# LEDControllerBoard.net
KiCad netlist of a schematic drawn in EAGLE
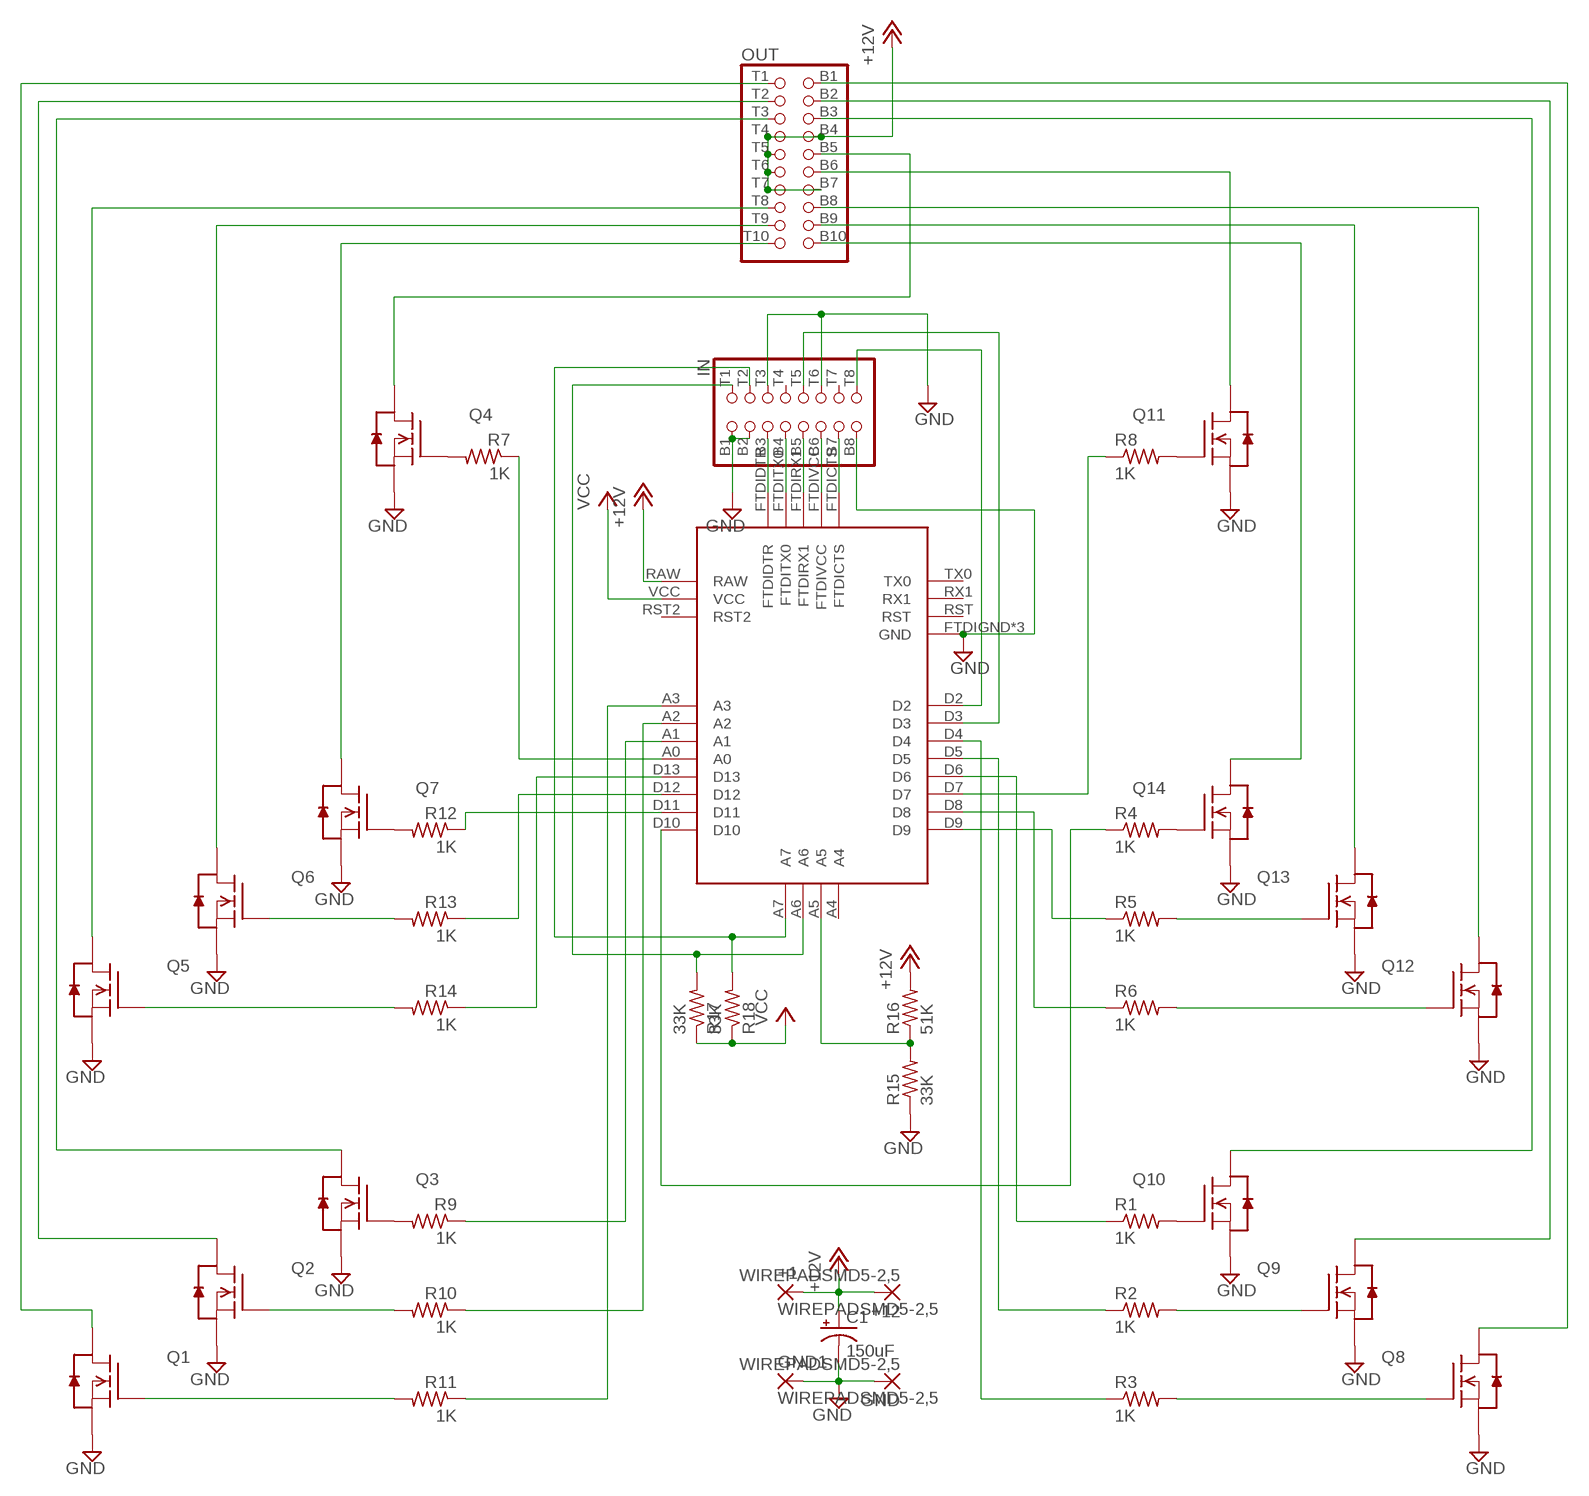
[diagram p0: schematic, sheet 1]

(export (version "E")
  (design (tool "Eeschema 10.0.6"))
  (components
    (comp (ref "+1")
      (value "WIREPADSMD5-2,5")
      (footprint "eagle-import:5-2,5")
      (libsource (lib "eagle-import") (part "WIREPADSMD5-2,5"))
    )
    (comp (ref "+12")
      (value "WIREPADSMD5-2,5")
      (footprint "eagle-import:5-2,5")
      (libsource (lib "eagle-import") (part "WIREPADSMD5-2,5"))
    )
    (comp (ref "C1")
      (value "150uF")
      (footprint "eagle-import:PANASONIC_D")
      (libsource (lib "eagle-import") (part "CPOL-USD"))
    )
    (comp (ref "GND")
      (value "WIREPADSMD5-2,5")
      (footprint "eagle-import:5-2,5")
      (libsource (lib "eagle-import") (part "WIREPADSMD5-2,5"))
    )
    (comp (ref "GND1")
      (value "WIREPADSMD5-2,5")
      (footprint "eagle-import:5-2,5")
      (libsource (lib "eagle-import") (part "WIREPADSMD5-2,5"))
    )
    (comp (ref "IN")
      (value "PINHD-2X8/EDGE")
      (footprint "eagle-import:2X8_EDGE")
      (libsource (lib "eagle-import") (part "PINHD-2X8/EDGE"))
    )
    (comp (ref "OUT")
      (value "PINHD-2X10/EDGE")
      (footprint "eagle-import:2X10_EDGE")
      (libsource (lib "eagle-import") (part "PINHD-2X10/EDGE"))
    )
    (comp (ref "Q1")
      (value "FDC653NSSOT6")
      (footprint "eagle-import:SSOT6")
      (libsource (lib "eagle-import") (part "FDC653NSSOT6"))
    )
    (comp (ref "Q2")
      (value "FDC653NSSOT6")
      (footprint "eagle-import:SSOT6")
      (libsource (lib "eagle-import") (part "FDC653NSSOT6"))
    )
    (comp (ref "Q3")
      (value "FDC653NSSOT6")
      (footprint "eagle-import:SSOT6")
      (libsource (lib "eagle-import") (part "FDC653NSSOT6"))
    )
    (comp (ref "Q4")
      (value "FDC653NSSOT6")
      (footprint "eagle-import:SSOT6")
      (libsource (lib "eagle-import") (part "FDC653NSSOT6"))
    )
    (comp (ref "Q5")
      (value "FDC653NSSOT6")
      (footprint "eagle-import:SSOT6")
      (libsource (lib "eagle-import") (part "FDC653NSSOT6"))
    )
    (comp (ref "Q6")
      (value "FDC653NSSOT6")
      (footprint "eagle-import:SSOT6")
      (libsource (lib "eagle-import") (part "FDC653NSSOT6"))
    )
    (comp (ref "Q7")
      (value "FDC653NSSOT6")
      (footprint "eagle-import:SSOT6")
      (libsource (lib "eagle-import") (part "FDC653NSSOT6"))
    )
    (comp (ref "Q8")
      (value "FDC653NSSOT6")
      (footprint "eagle-import:SSOT6")
      (libsource (lib "eagle-import") (part "FDC653NSSOT6"))
    )
    (comp (ref "Q9")
      (value "FDC653NSSOT6")
      (footprint "eagle-import:SSOT6")
      (libsource (lib "eagle-import") (part "FDC653NSSOT6"))
    )
    (comp (ref "Q10")
      (value "FDC653NSSOT6")
      (footprint "eagle-import:SSOT6")
      (libsource (lib "eagle-import") (part "FDC653NSSOT6"))
    )
    (comp (ref "Q11")
      (value "FDC653NSSOT6")
      (footprint "eagle-import:SSOT6")
      (libsource (lib "eagle-import") (part "FDC653NSSOT6"))
    )
    (comp (ref "Q12")
      (value "FDC653NSSOT6")
      (footprint "eagle-import:SSOT6")
      (libsource (lib "eagle-import") (part "FDC653NSSOT6"))
    )
    (comp (ref "Q13")
      (value "FDC653NSSOT6")
      (footprint "eagle-import:SSOT6")
      (libsource (lib "eagle-import") (part "FDC653NSSOT6"))
    )
    (comp (ref "Q14")
      (value "FDC653NSSOT6")
      (footprint "eagle-import:SSOT6")
      (libsource (lib "eagle-import") (part "FDC653NSSOT6"))
    )
    (comp (ref "R1")
      (value "1K")
      (footprint "eagle-import:R0603")
      (libsource (lib "eagle-import") (part "R-US_R0603"))
    )
    (comp (ref "R2")
      (value "1K")
      (footprint "eagle-import:R0603")
      (libsource (lib "eagle-import") (part "R-US_R0603"))
    )
    (comp (ref "R3")
      (value "1K")
      (footprint "eagle-import:R0603")
      (libsource (lib "eagle-import") (part "R-US_R0603"))
    )
    (comp (ref "R4")
      (value "1K")
      (footprint "eagle-import:R0603")
      (libsource (lib "eagle-import") (part "R-US_R0603"))
    )
    (comp (ref "R5")
      (value "1K")
      (footprint "eagle-import:R0603")
      (libsource (lib "eagle-import") (part "R-US_R0603"))
    )
    (comp (ref "R6")
      (value "1K")
      (footprint "eagle-import:R0603")
      (libsource (lib "eagle-import") (part "R-US_R0603"))
    )
    (comp (ref "R7")
      (value "1K")
      (footprint "eagle-import:R0603")
      (libsource (lib "eagle-import") (part "R-US_R0603"))
    )
    (comp (ref "R8")
      (value "1K")
      (footprint "eagle-import:R0603")
      (libsource (lib "eagle-import") (part "R-US_R0603"))
    )
    (comp (ref "R9")
      (value "1K")
      (footprint "eagle-import:R0603")
      (libsource (lib "eagle-import") (part "R-US_R0603"))
    )
    (comp (ref "R10")
      (value "1K")
      (footprint "eagle-import:R0603")
      (libsource (lib "eagle-import") (part "R-US_R0603"))
    )
    (comp (ref "R11")
      (value "1K")
      (footprint "eagle-import:R0603")
      (libsource (lib "eagle-import") (part "R-US_R0603"))
    )
    (comp (ref "R12")
      (value "1K")
      (footprint "eagle-import:R0603")
      (libsource (lib "eagle-import") (part "R-US_R0603"))
    )
    (comp (ref "R13")
      (value "1K")
      (footprint "eagle-import:R0603")
      (libsource (lib "eagle-import") (part "R-US_R0603"))
    )
    (comp (ref "R14")
      (value "1K")
      (footprint "eagle-import:R0603")
      (libsource (lib "eagle-import") (part "R-US_R0603"))
    )
    (comp (ref "R15")
      (value "33K")
      (footprint "eagle-import:R0603")
      (libsource (lib "eagle-import") (part "R-US_R0603"))
    )
    (comp (ref "R16")
      (value "51K")
      (footprint "eagle-import:R0603")
      (libsource (lib "eagle-import") (part "R-US_R0603"))
    )
    (comp (ref "R17")
      (value "33K")
      (footprint "eagle-import:R0603")
      (libsource (lib "eagle-import") (part "R-US_R0603"))
    )
    (comp (ref "R18")
      (value "33K")
      (footprint "eagle-import:R0603")
      (libsource (lib "eagle-import") (part "R-US_R0603"))
    )
    (comp (ref "U$15")
      (value "ARDUINOPROMINI")
      (footprint "eagle-import:ARDUINOPROMINI")
      (libsource (lib "eagle-import") (part "ARDUINOPROMINI"))
    )
  )
  (nets
    (net (code "1") (name "+12V") (class "Default")
      (node (ref "+1") (pin "1") (pinfunction "P_1") (pintype "passive"))
      (node (ref "+12") (pin "1") (pinfunction "P_1") (pintype "passive"))
      (node (ref "C1") (pin "+") (pinfunction "+_+") (pintype "passive"))
      (node (ref "OUT") (pin "B4") (pinfunction "8_B4") (pintype "passive"))
      (node (ref "OUT") (pin "B7") (pinfunction "14_B7") (pintype "passive"))
      (node (ref "OUT") (pin "T4") (pinfunction "7_T4") (pintype "passive"))
      (node (ref "OUT") (pin "T5") (pinfunction "9_T5") (pintype "passive"))
      (node (ref "OUT") (pin "T6") (pinfunction "11_T6") (pintype "passive"))
      (node (ref "OUT") (pin "T7") (pinfunction "13_T7") (pintype "passive"))
      (node (ref "R16") (pin "2") (pinfunction "2_2") (pintype "passive"))
      (node (ref "U$15") (pin "RAW") (pinfunction "RAW_RAW") (pintype "bidirectional"))
    )
    (net (code "2") (name "GND") (class "Default")
      (node (ref "C1") (pin "-") (pinfunction "-_-") (pintype "passive"))
      (node (ref "GND") (pin "1") (pinfunction "P_1") (pintype "passive"))
      (node (ref "GND1") (pin "1") (pinfunction "P_1") (pintype "passive"))
      (node (ref "IN") (pin "B1") (pinfunction "2_B1") (pintype "passive"))
      (node (ref "IN") (pin "B2") (pinfunction "4_B2") (pintype "passive"))
      (node (ref "IN") (pin "B8") (pinfunction "16_B8") (pintype "passive"))
      (node (ref "IN") (pin "T3") (pinfunction "5_T3") (pintype "passive"))
      (node (ref "IN") (pin "T6") (pinfunction "11_T6") (pintype "passive"))
      (node (ref "Q1") (pin "4") (pinfunction "S_4") (pintype "passive"))
      (node (ref "Q10") (pin "4") (pinfunction "S_4") (pintype "passive"))
      (node (ref "Q11") (pin "4") (pinfunction "S_4") (pintype "passive"))
      (node (ref "Q12") (pin "4") (pinfunction "S_4") (pintype "passive"))
      (node (ref "Q13") (pin "4") (pinfunction "S_4") (pintype "passive"))
      (node (ref "Q14") (pin "4") (pinfunction "S_4") (pintype "passive"))
      (node (ref "Q2") (pin "4") (pinfunction "S_4") (pintype "passive"))
      (node (ref "Q3") (pin "4") (pinfunction "S_4") (pintype "passive"))
      (node (ref "Q4") (pin "4") (pinfunction "S_4") (pintype "passive"))
      (node (ref "Q5") (pin "4") (pinfunction "S_4") (pintype "passive"))
      (node (ref "Q6") (pin "4") (pinfunction "S_4") (pintype "passive"))
      (node (ref "Q7") (pin "4") (pinfunction "S_4") (pintype "passive"))
      (node (ref "Q8") (pin "4") (pinfunction "S_4") (pintype "passive"))
      (node (ref "Q9") (pin "4") (pinfunction "S_4") (pintype "passive"))
      (node (ref "R15") (pin "1") (pinfunction "1_1") (pintype "passive"))
      (node (ref "U$15") (pin "FTDIGND") (pinfunction "GND_FTDIGND") (pintype "bidirectional"))
      (node (ref "U$15") (pin "GND") (pinfunction "GND_GND") (pintype "bidirectional"))
      (node (ref "U$15") (pin "GND2") (pinfunction "GND_GND2") (pintype "bidirectional"))
    )
    (net (code "3") (name "Net-(IN-1)") (class "Default")
      (node (ref "IN") (pin "T1") (pinfunction "1_T1") (pintype "passive"))
      (node (ref "R17") (pin "2") (pinfunction "2_2") (pintype "passive"))
      (node (ref "U$15") (pin "A6") (pinfunction "A6_A6") (pintype "bidirectional"))
    )
    (net (code "4") (name "Net-(IN-3)") (class "Default")
      (node (ref "IN") (pin "T2") (pinfunction "3_T2") (pintype "passive"))
      (node (ref "R18") (pin "2") (pinfunction "2_2") (pintype "passive"))
      (node (ref "U$15") (pin "A7") (pinfunction "A7_A7") (pintype "bidirectional"))
    )
    (net (code "5") (name "Net-(IN-6)") (class "Default")
      (node (ref "IN") (pin "B3") (pinfunction "6_B3") (pintype "passive"))
      (node (ref "U$15") (pin "FTDIDTR") (pinfunction "FTDIDTR_FTDIDTR") (pintype "bidirectional"))
    )
    (net (code "6") (name "Net-(IN-8)") (class "Default")
      (node (ref "IN") (pin "B4") (pinfunction "8_B4") (pintype "passive"))
      (node (ref "U$15") (pin "FTDITX0") (pinfunction "FTDITX0_FTDITX0") (pintype "bidirectional"))
    )
    (net (code "7") (name "Net-(IN-9)") (class "Default")
      (node (ref "IN") (pin "T5") (pinfunction "9_T5") (pintype "passive"))
      (node (ref "U$15") (pin "D3") (pinfunction "D3_D3") (pintype "bidirectional"))
    )
    (net (code "8") (name "Net-(IN-10)") (class "Default")
      (node (ref "IN") (pin "B5") (pinfunction "10_B5") (pintype "passive"))
      (node (ref "U$15") (pin "FTDIRX1") (pinfunction "FTDIRX1_FTDIRX1") (pintype "bidirectional"))
    )
    (net (code "9") (name "Net-(IN-12)") (class "Default")
      (node (ref "IN") (pin "B6") (pinfunction "12_B6") (pintype "passive"))
      (node (ref "U$15") (pin "FTDIVCC") (pinfunction "FTDIVCC_FTDIVCC") (pintype "bidirectional"))
    )
    (net (code "10") (name "Net-(IN-14)") (class "Default")
      (node (ref "IN") (pin "B7") (pinfunction "14_B7") (pintype "passive"))
      (node (ref "U$15") (pin "FTDICTS") (pinfunction "FTDICTS_FTDICTS") (pintype "bidirectional"))
    )
    (net (code "11") (name "Net-(IN-15)") (class "Default")
      (node (ref "IN") (pin "T8") (pinfunction "15_T8") (pintype "passive"))
      (node (ref "U$15") (pin "D2") (pinfunction "D2_D2") (pintype "bidirectional"))
    )
    (net (code "12") (name "Net-(OUT-1)") (class "Default")
      (node (ref "OUT") (pin "T1") (pinfunction "1_T1") (pintype "passive"))
      (node (ref "Q1") (pin "1") (pinfunction "D_1") (pintype "passive"))
      (node (ref "Q1") (pin "2") (pinfunction "D_2") (pintype "passive"))
      (node (ref "Q1") (pin "5") (pinfunction "D_5") (pintype "passive"))
      (node (ref "Q1") (pin "6") (pinfunction "D_6") (pintype "passive"))
    )
    (net (code "13") (name "Net-(OUT-2)") (class "Default")
      (node (ref "OUT") (pin "B1") (pinfunction "2_B1") (pintype "passive"))
      (node (ref "Q8") (pin "1") (pinfunction "D_1") (pintype "passive"))
      (node (ref "Q8") (pin "2") (pinfunction "D_2") (pintype "passive"))
      (node (ref "Q8") (pin "5") (pinfunction "D_5") (pintype "passive"))
      (node (ref "Q8") (pin "6") (pinfunction "D_6") (pintype "passive"))
    )
    (net (code "14") (name "Net-(OUT-3)") (class "Default")
      (node (ref "OUT") (pin "T2") (pinfunction "3_T2") (pintype "passive"))
      (node (ref "Q2") (pin "1") (pinfunction "D_1") (pintype "passive"))
      (node (ref "Q2") (pin "2") (pinfunction "D_2") (pintype "passive"))
      (node (ref "Q2") (pin "5") (pinfunction "D_5") (pintype "passive"))
      (node (ref "Q2") (pin "6") (pinfunction "D_6") (pintype "passive"))
    )
    (net (code "15") (name "Net-(OUT-4)") (class "Default")
      (node (ref "OUT") (pin "B2") (pinfunction "4_B2") (pintype "passive"))
      (node (ref "Q9") (pin "1") (pinfunction "D_1") (pintype "passive"))
      (node (ref "Q9") (pin "2") (pinfunction "D_2") (pintype "passive"))
      (node (ref "Q9") (pin "5") (pinfunction "D_5") (pintype "passive"))
      (node (ref "Q9") (pin "6") (pinfunction "D_6") (pintype "passive"))
    )
    (net (code "16") (name "Net-(OUT-5)") (class "Default")
      (node (ref "OUT") (pin "T3") (pinfunction "5_T3") (pintype "passive"))
      (node (ref "Q3") (pin "1") (pinfunction "D_1") (pintype "passive"))
      (node (ref "Q3") (pin "2") (pinfunction "D_2") (pintype "passive"))
      (node (ref "Q3") (pin "5") (pinfunction "D_5") (pintype "passive"))
      (node (ref "Q3") (pin "6") (pinfunction "D_6") (pintype "passive"))
    )
    (net (code "17") (name "Net-(OUT-6)") (class "Default")
      (node (ref "OUT") (pin "B3") (pinfunction "6_B3") (pintype "passive"))
      (node (ref "Q10") (pin "1") (pinfunction "D_1") (pintype "passive"))
      (node (ref "Q10") (pin "2") (pinfunction "D_2") (pintype "passive"))
      (node (ref "Q10") (pin "5") (pinfunction "D_5") (pintype "passive"))
      (node (ref "Q10") (pin "6") (pinfunction "D_6") (pintype "passive"))
    )
    (net (code "18") (name "Net-(OUT-10)") (class "Default")
      (node (ref "OUT") (pin "B5") (pinfunction "10_B5") (pintype "passive"))
      (node (ref "Q4") (pin "1") (pinfunction "D_1") (pintype "passive"))
      (node (ref "Q4") (pin "2") (pinfunction "D_2") (pintype "passive"))
      (node (ref "Q4") (pin "5") (pinfunction "D_5") (pintype "passive"))
      (node (ref "Q4") (pin "6") (pinfunction "D_6") (pintype "passive"))
    )
    (net (code "19") (name "Net-(OUT-12)") (class "Default")
      (node (ref "OUT") (pin "B6") (pinfunction "12_B6") (pintype "passive"))
      (node (ref "Q11") (pin "1") (pinfunction "D_1") (pintype "passive"))
      (node (ref "Q11") (pin "2") (pinfunction "D_2") (pintype "passive"))
      (node (ref "Q11") (pin "5") (pinfunction "D_5") (pintype "passive"))
      (node (ref "Q11") (pin "6") (pinfunction "D_6") (pintype "passive"))
    )
    (net (code "20") (name "Net-(OUT-15)") (class "Default")
      (node (ref "OUT") (pin "T8") (pinfunction "15_T8") (pintype "passive"))
      (node (ref "Q5") (pin "1") (pinfunction "D_1") (pintype "passive"))
      (node (ref "Q5") (pin "2") (pinfunction "D_2") (pintype "passive"))
      (node (ref "Q5") (pin "5") (pinfunction "D_5") (pintype "passive"))
      (node (ref "Q5") (pin "6") (pinfunction "D_6") (pintype "passive"))
    )
    (net (code "21") (name "Net-(OUT-16)") (class "Default")
      (node (ref "OUT") (pin "B8") (pinfunction "16_B8") (pintype "passive"))
      (node (ref "Q12") (pin "1") (pinfunction "D_1") (pintype "passive"))
      (node (ref "Q12") (pin "2") (pinfunction "D_2") (pintype "passive"))
      (node (ref "Q12") (pin "5") (pinfunction "D_5") (pintype "passive"))
      (node (ref "Q12") (pin "6") (pinfunction "D_6") (pintype "passive"))
    )
    (net (code "22") (name "Net-(OUT-17)") (class "Default")
      (node (ref "OUT") (pin "T9") (pinfunction "17_T9") (pintype "passive"))
      (node (ref "Q6") (pin "1") (pinfunction "D_1") (pintype "passive"))
      (node (ref "Q6") (pin "2") (pinfunction "D_2") (pintype "passive"))
      (node (ref "Q6") (pin "5") (pinfunction "D_5") (pintype "passive"))
      (node (ref "Q6") (pin "6") (pinfunction "D_6") (pintype "passive"))
    )
    (net (code "23") (name "Net-(OUT-18)") (class "Default")
      (node (ref "OUT") (pin "B9") (pinfunction "18_B9") (pintype "passive"))
      (node (ref "Q13") (pin "1") (pinfunction "D_1") (pintype "passive"))
      (node (ref "Q13") (pin "2") (pinfunction "D_2") (pintype "passive"))
      (node (ref "Q13") (pin "5") (pinfunction "D_5") (pintype "passive"))
      (node (ref "Q13") (pin "6") (pinfunction "D_6") (pintype "passive"))
    )
    (net (code "24") (name "Net-(OUT-19)") (class "Default")
      (node (ref "OUT") (pin "T10") (pinfunction "19_T10") (pintype "passive"))
      (node (ref "Q7") (pin "1") (pinfunction "D_1") (pintype "passive"))
      (node (ref "Q7") (pin "2") (pinfunction "D_2") (pintype "passive"))
      (node (ref "Q7") (pin "5") (pinfunction "D_5") (pintype "passive"))
      (node (ref "Q7") (pin "6") (pinfunction "D_6") (pintype "passive"))
    )
    (net (code "25") (name "Net-(OUT-20)") (class "Default")
      (node (ref "OUT") (pin "B10") (pinfunction "20_B10") (pintype "passive"))
      (node (ref "Q14") (pin "1") (pinfunction "D_1") (pintype "passive"))
      (node (ref "Q14") (pin "2") (pinfunction "D_2") (pintype "passive"))
      (node (ref "Q14") (pin "5") (pinfunction "D_5") (pintype "passive"))
      (node (ref "Q14") (pin "6") (pinfunction "D_6") (pintype "passive"))
    )
    (net (code "26") (name "Net-(Q1-G)") (class "Default")
      (node (ref "Q1") (pin "3") (pinfunction "G_3") (pintype "passive"))
      (node (ref "R11") (pin "2") (pinfunction "2_2") (pintype "passive"))
    )
    (net (code "27") (name "Net-(Q2-G)") (class "Default")
      (node (ref "Q2") (pin "3") (pinfunction "G_3") (pintype "passive"))
      (node (ref "R10") (pin "2") (pinfunction "2_2") (pintype "passive"))
    )
    (net (code "28") (name "Net-(Q3-G)") (class "Default")
      (node (ref "Q3") (pin "3") (pinfunction "G_3") (pintype "passive"))
      (node (ref "R9") (pin "2") (pinfunction "2_2") (pintype "passive"))
    )
    (net (code "29") (name "Net-(Q4-G)") (class "Default")
      (node (ref "Q4") (pin "3") (pinfunction "G_3") (pintype "passive"))
      (node (ref "R7") (pin "2") (pinfunction "2_2") (pintype "passive"))
    )
    (net (code "30") (name "Net-(Q5-G)") (class "Default")
      (node (ref "Q5") (pin "3") (pinfunction "G_3") (pintype "passive"))
      (node (ref "R14") (pin "2") (pinfunction "2_2") (pintype "passive"))
    )
    (net (code "31") (name "Net-(Q6-G)") (class "Default")
      (node (ref "Q6") (pin "3") (pinfunction "G_3") (pintype "passive"))
      (node (ref "R13") (pin "2") (pinfunction "2_2") (pintype "passive"))
    )
    (net (code "32") (name "Net-(Q7-G)") (class "Default")
      (node (ref "Q7") (pin "3") (pinfunction "G_3") (pintype "passive"))
      (node (ref "R12") (pin "2") (pinfunction "2_2") (pintype "passive"))
    )
    (net (code "33") (name "Net-(Q8-G)") (class "Default")
      (node (ref "Q8") (pin "3") (pinfunction "G_3") (pintype "passive"))
      (node (ref "R3") (pin "2") (pinfunction "2_2") (pintype "passive"))
    )
    (net (code "34") (name "Net-(Q9-G)") (class "Default")
      (node (ref "Q9") (pin "3") (pinfunction "G_3") (pintype "passive"))
      (node (ref "R2") (pin "2") (pinfunction "2_2") (pintype "passive"))
    )
    (net (code "35") (name "Net-(Q10-G)") (class "Default")
      (node (ref "Q10") (pin "3") (pinfunction "G_3") (pintype "passive"))
      (node (ref "R1") (pin "2") (pinfunction "2_2") (pintype "passive"))
    )
    (net (code "36") (name "Net-(Q11-G)") (class "Default")
      (node (ref "Q11") (pin "3") (pinfunction "G_3") (pintype "passive"))
      (node (ref "R8") (pin "2") (pinfunction "2_2") (pintype "passive"))
    )
    (net (code "37") (name "Net-(Q12-G)") (class "Default")
      (node (ref "Q12") (pin "3") (pinfunction "G_3") (pintype "passive"))
      (node (ref "R6") (pin "2") (pinfunction "2_2") (pintype "passive"))
    )
    (net (code "38") (name "Net-(Q13-G)") (class "Default")
      (node (ref "Q13") (pin "3") (pinfunction "G_3") (pintype "passive"))
      (node (ref "R5") (pin "2") (pinfunction "2_2") (pintype "passive"))
    )
    (net (code "39") (name "Net-(Q14-G)") (class "Default")
      (node (ref "Q14") (pin "3") (pinfunction "G_3") (pintype "passive"))
      (node (ref "R4") (pin "2") (pinfunction "2_2") (pintype "passive"))
    )
    (net (code "40") (name "Net-(R1-Pad1)") (class "Default")
      (node (ref "R1") (pin "1") (pinfunction "1_1") (pintype "passive"))
      (node (ref "U$15") (pin "D6") (pinfunction "D6_D6") (pintype "bidirectional"))
    )
    (net (code "41") (name "Net-(R2-Pad1)") (class "Default")
      (node (ref "R2") (pin "1") (pinfunction "1_1") (pintype "passive"))
      (node (ref "U$15") (pin "D5") (pinfunction "D5_D5") (pintype "bidirectional"))
    )
    (net (code "42") (name "Net-(R3-Pad1)") (class "Default")
      (node (ref "R3") (pin "1") (pinfunction "1_1") (pintype "passive"))
      (node (ref "U$15") (pin "D4") (pinfunction "D4_D4") (pintype "bidirectional"))
    )
    (net (code "43") (name "Net-(R4-Pad1)") (class "Default")
      (node (ref "R4") (pin "1") (pinfunction "1_1") (pintype "passive"))
      (node (ref "U$15") (pin "D10") (pinfunction "D10_D10") (pintype "bidirectional"))
    )
    (net (code "44") (name "Net-(R5-Pad1)") (class "Default")
      (node (ref "R5") (pin "1") (pinfunction "1_1") (pintype "passive"))
      (node (ref "U$15") (pin "D9") (pinfunction "D9_D9") (pintype "bidirectional"))
    )
    (net (code "45") (name "Net-(R6-Pad1)") (class "Default")
      (node (ref "R6") (pin "1") (pinfunction "1_1") (pintype "passive"))
      (node (ref "U$15") (pin "D8") (pinfunction "D8_D8") (pintype "bidirectional"))
    )
    (net (code "46") (name "Net-(R7-Pad1)") (class "Default")
      (node (ref "R7") (pin "1") (pinfunction "1_1") (pintype "passive"))
      (node (ref "U$15") (pin "A0") (pinfunction "A0_A0") (pintype "bidirectional"))
    )
    (net (code "47") (name "Net-(R8-Pad1)") (class "Default")
      (node (ref "R8") (pin "1") (pinfunction "1_1") (pintype "passive"))
      (node (ref "U$15") (pin "D7") (pinfunction "D7_D7") (pintype "bidirectional"))
    )
    (net (code "48") (name "Net-(R9-Pad1)") (class "Default")
      (node (ref "R9") (pin "1") (pinfunction "1_1") (pintype "passive"))
      (node (ref "U$15") (pin "A1") (pinfunction "A1_A1") (pintype "bidirectional"))
    )
    (net (code "49") (name "Net-(R10-Pad1)") (class "Default")
      (node (ref "R10") (pin "1") (pinfunction "1_1") (pintype "passive"))
      (node (ref "U$15") (pin "A2") (pinfunction "A2_A2") (pintype "bidirectional"))
    )
    (net (code "50") (name "Net-(R11-Pad1)") (class "Default")
      (node (ref "R11") (pin "1") (pinfunction "1_1") (pintype "passive"))
      (node (ref "U$15") (pin "A3") (pinfunction "A3_A3") (pintype "bidirectional"))
    )
    (net (code "51") (name "Net-(R12-Pad1)") (class "Default")
      (node (ref "R12") (pin "1") (pinfunction "1_1") (pintype "passive"))
      (node (ref "U$15") (pin "D11") (pinfunction "D11_D11") (pintype "bidirectional"))
    )
    (net (code "52") (name "Net-(R13-Pad1)") (class "Default")
      (node (ref "R13") (pin "1") (pinfunction "1_1") (pintype "passive"))
      (node (ref "U$15") (pin "D12") (pinfunction "D12_D12") (pintype "bidirectional"))
    )
    (net (code "53") (name "Net-(R14-Pad1)") (class "Default")
      (node (ref "R14") (pin "1") (pinfunction "1_1") (pintype "passive"))
      (node (ref "U$15") (pin "D13") (pinfunction "D13_D13") (pintype "bidirectional"))
    )
    (net (code "54") (name "Net-(R15-Pad2)") (class "Default")
      (node (ref "R15") (pin "2") (pinfunction "2_2") (pintype "passive"))
      (node (ref "R16") (pin "1") (pinfunction "1_1") (pintype "passive"))
      (node (ref "U$15") (pin "A5") (pinfunction "A5_A5") (pintype "bidirectional"))
    )
    (net (code "55") (name "VCC") (class "Default")
      (node (ref "R17") (pin "1") (pinfunction "1_1") (pintype "passive"))
      (node (ref "R18") (pin "1") (pinfunction "1_1") (pintype "passive"))
      (node (ref "U$15") (pin "VCC") (pinfunction "VCC_VCC") (pintype "bidirectional"))
    )
    (net (code "56") (name "unconnected-(IN-7-PadT4)") (class "Default")
      (node (ref "IN") (pin "T4") (pinfunction "7_T4") (pintype "passive"))
    )
    (net (code "57") (name "unconnected-(IN-13-PadT7)") (class "Default")
      (node (ref "IN") (pin "T7") (pinfunction "13_T7") (pintype "passive"))
    )
    (net (code "58") (name "unconnected-(U$15-PadA4)") (class "Default")
      (node (ref "U$15") (pin "A4") (pinfunction "A4_A4") (pintype "bidirectional"))
    )
    (net (code "59") (name "unconnected-(U$15-PadRST)") (class "Default")
      (node (ref "U$15") (pin "RST") (pinfunction "RST_RST") (pintype "bidirectional"))
    )
    (net (code "60") (name "unconnected-(U$15-PadRST2)") (class "Default")
      (node (ref "U$15") (pin "RST2") (pinfunction "RST2_RST2") (pintype "bidirectional"))
    )
    (net (code "61") (name "unconnected-(U$15-PadRX1)") (class "Default")
      (node (ref "U$15") (pin "RX1") (pinfunction "RX1_RX1") (pintype "bidirectional"))
    )
    (net (code "62") (name "unconnected-(U$15-PadTX0)") (class "Default")
      (node (ref "U$15") (pin "TX0") (pinfunction "TX0_TX0") (pintype "bidirectional"))
    )
  )
)
